# WSPRShield.net
KiCad netlist of a schematic drawn in Altium Designer
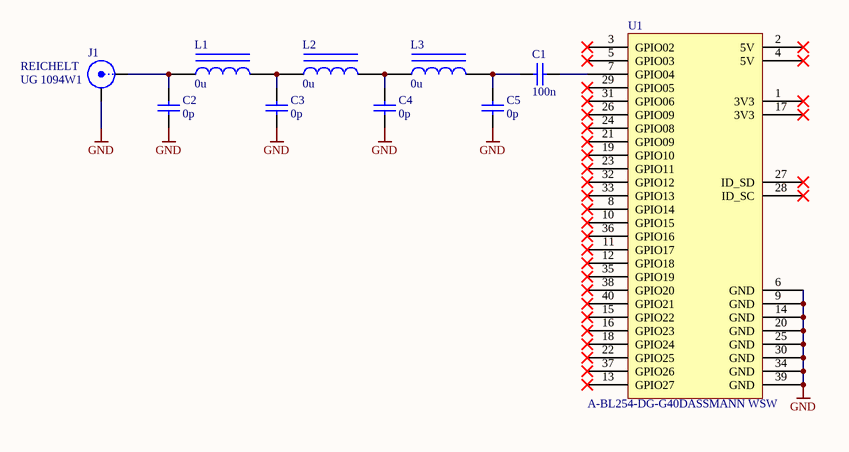
[diagram p0: WSPRShield.SchDoc]

(export (version "E")
  (design (tool "Eeschema 10.0.6"))
  (components
    (comp (ref "C1")
      (value "100n")
      (footprint "CER-CO-5MM")
      (fields
        (field (name "VOLTAGE") "100")
        (field (name "MANUFACTURER") "Miscellaneous")
        (field (name "Comment") "Capacitor")
      )
      (libsource (lib "ROLAND-LIB") (part "Capacitor"))
    )
    (comp (ref "C2")
      (value "0p")
      (footprint "CER-CO-5MM")
      (fields
        (field (name "VOLTAGE") "100")
        (field (name "MANUFACTURER") "Miscellaneous")
        (field (name "Comment") "Capacitor")
      )
      (libsource (lib "ROLAND-LIB") (part "Capacitor"))
    )
    (comp (ref "C3")
      (value "0p")
      (footprint "CER-CO-5MM")
      (fields
        (field (name "VOLTAGE") "100")
        (field (name "MANUFACTURER") "Miscellaneous")
        (field (name "Comment") "Capacitor")
      )
      (libsource (lib "ROLAND-LIB") (part "Capacitor"))
    )
    (comp (ref "C4")
      (value "0p")
      (footprint "CER-CO-5MM")
      (fields
        (field (name "VOLTAGE") "100")
        (field (name "MANUFACTURER") "Miscellaneous")
        (field (name "Comment") "Capacitor")
      )
      (libsource (lib "ROLAND-LIB") (part "Capacitor"))
    )
    (comp (ref "C5")
      (value "0p")
      (footprint "CER-CO-5MM")
      (fields
        (field (name "VOLTAGE") "100")
        (field (name "MANUFACTURER") "Miscellaneous")
        (field (name "Comment") "Capacitor")
      )
      (libsource (lib "ROLAND-LIB") (part "Capacitor"))
    )
    (comp (ref "J1")
      (value "COAX")
      (footprint "REICHELT_UG1094W1")
      (fields (field (name "MANUFACTURER") "REICHELT") (field (name "TYPE") "UG 1094W1"))
      (libsource (lib "ROLAND-LIB") (part "COAX"))
    )
    (comp (ref "L1")
      (value "0u")
      (footprint "T37-6")
      (fields (field (name "Comment") "Inductor (IronCore)"))
      (libsource (lib "ROLAND-LIB") (part "Inductor (IronCore)"))
    )
    (comp (ref "L2")
      (value "0u")
      (footprint "T37-6")
      (fields (field (name "Comment") "Inductor (IronCore)"))
      (libsource (lib "ROLAND-LIB") (part "Inductor (IronCore)"))
    )
    (comp (ref "L3")
      (value "0u")
      (footprint "T37-6")
      (fields (field (name "Comment") "Inductor (IronCore)"))
      (libsource (lib "ROLAND-LIB") (part "Inductor (IronCore)"))
    )
    (comp (ref "U1")
      (value "RaspberryPiB")
      (footprint "RASPI_BPHAT")
      (fields (field (name "TYPE") "A-BL254-DG-G40DASSMANN WSW") (field (name "MANUFACTURER") "ASSMANN"))
      (libsource (lib "ROLAND-LIB") (part "RaspberryPiB"))
    )
  )
  (nets
    (net (code "1") (name "GND") (class "Default")
      (node (ref "C2") (pin "1") (pinfunction "1_1") (pintype "passive"))
      (node (ref "C3") (pin "1") (pinfunction "1_1") (pintype "passive"))
      (node (ref "C4") (pin "1") (pinfunction "1_1") (pintype "passive"))
      (node (ref "C5") (pin "1") (pinfunction "1_1") (pintype "passive"))
      (node (ref "J1") (pin "2") (pinfunction "Y_2") (pintype "passive"))
      (node (ref "U1") (pin "14") (pinfunction "GND_14") (pintype "passive"))
      (node (ref "U1") (pin "20") (pinfunction "GND_20") (pintype "passive"))
      (node (ref "U1") (pin "25") (pinfunction "GND_25") (pintype "passive"))
      (node (ref "U1") (pin "30") (pinfunction "GND_30") (pintype "passive"))
      (node (ref "U1") (pin "34") (pinfunction "GND_34") (pintype "passive"))
      (node (ref "U1") (pin "39") (pinfunction "GND_39") (pintype "passive"))
      (node (ref "U1") (pin "6") (pinfunction "GND_6") (pintype "passive"))
      (node (ref "U1") (pin "9") (pinfunction "GND_9") (pintype "passive"))
    )
    (net (code "2") (name "Net-(C1-Pad2)") (class "Default")
      (node (ref "C1") (pin "2") (pinfunction "2_2") (pintype "passive"))
      (node (ref "C5") (pin "2") (pinfunction "2_2") (pintype "passive"))
      (node (ref "L3") (pin "2") (pinfunction "2_2") (pintype "passive"))
    )
    (net (code "3") (name "Net-(C3-Pad2)") (class "Default")
      (node (ref "C3") (pin "2") (pinfunction "2_2") (pintype "passive"))
      (node (ref "L1") (pin "2") (pinfunction "2_2") (pintype "passive"))
      (node (ref "L2") (pin "1") (pinfunction "1_1") (pintype "passive"))
    )
    (net (code "4") (name "Net-(C4-Pad2)") (class "Default")
      (node (ref "C4") (pin "2") (pinfunction "2_2") (pintype "passive"))
      (node (ref "L2") (pin "2") (pinfunction "2_2") (pintype "passive"))
      (node (ref "L3") (pin "1") (pinfunction "1_1") (pintype "passive"))
    )
    (net (code "5") (name "Net-(J1-X)") (class "Default")
      (node (ref "C2") (pin "2") (pinfunction "2_2") (pintype "passive"))
      (node (ref "J1") (pin "1") (pinfunction "X_1") (pintype "passive"))
      (node (ref "L1") (pin "1") (pinfunction "1_1") (pintype "passive"))
    )
    (net (code "6") (name "Net-(U1-GPIO04)") (class "Default")
      (node (ref "C1") (pin "1") (pinfunction "1_1") (pintype "passive"))
      (node (ref "U1") (pin "7") (pinfunction "GPIO04_7") (pintype "passive"))
    )
    (net (code "7") (name "unconnected-(U1-3V3-Pad1)") (class "Default")
      (node (ref "U1") (pin "1") (pinfunction "3V3_1") (pintype "passive+no_connect"))
    )
    (net (code "8") (name "unconnected-(U1-3V3-Pad17)") (class "Default")
      (node (ref "U1") (pin "17") (pinfunction "3V3_17") (pintype "passive+no_connect"))
    )
    (net (code "9") (name "unconnected-(U1-5V-Pad2)") (class "Default")
      (node (ref "U1") (pin "2") (pinfunction "5V_2") (pintype "passive+no_connect"))
    )
    (net (code "10") (name "unconnected-(U1-5V-Pad4)") (class "Default")
      (node (ref "U1") (pin "4") (pinfunction "5V_4") (pintype "passive+no_connect"))
    )
    (net (code "11") (name "unconnected-(U1-GPIO02-Pad3)") (class "Default")
      (node (ref "U1") (pin "3") (pinfunction "GPIO02_3") (pintype "passive+no_connect"))
    )
    (net (code "12") (name "unconnected-(U1-GPIO03-Pad5)") (class "Default")
      (node (ref "U1") (pin "5") (pinfunction "GPIO03_5") (pintype "passive+no_connect"))
    )
    (net (code "13") (name "unconnected-(U1-GPIO05-Pad29)") (class "Default")
      (node (ref "U1") (pin "29") (pinfunction "GPIO05_29") (pintype "passive+no_connect"))
    )
    (net (code "14") (name "unconnected-(U1-GPIO06-Pad31)") (class "Default")
      (node (ref "U1") (pin "31") (pinfunction "GPIO06_31") (pintype "passive+no_connect"))
    )
    (net (code "15") (name "unconnected-(U1-GPIO08-Pad24)") (class "Default")
      (node (ref "U1") (pin "24") (pinfunction "GPIO08_24") (pintype "passive+no_connect"))
    )
    (net (code "16") (name "unconnected-(U1-GPIO09-Pad21)") (class "Default")
      (node (ref "U1") (pin "21") (pinfunction "GPIO09_21") (pintype "passive+no_connect"))
    )
    (net (code "17") (name "unconnected-(U1-GPIO09-Pad26)") (class "Default")
      (node (ref "U1") (pin "26") (pinfunction "GPIO09_26") (pintype "passive+no_connect"))
    )
    (net (code "18") (name "unconnected-(U1-GPIO10-Pad19)") (class "Default")
      (node (ref "U1") (pin "19") (pinfunction "GPIO10_19") (pintype "passive+no_connect"))
    )
    (net (code "19") (name "unconnected-(U1-GPIO11-Pad23)") (class "Default")
      (node (ref "U1") (pin "23") (pinfunction "GPIO11_23") (pintype "passive+no_connect"))
    )
    (net (code "20") (name "unconnected-(U1-GPIO12-Pad32)") (class "Default")
      (node (ref "U1") (pin "32") (pinfunction "GPIO12_32") (pintype "passive+no_connect"))
    )
    (net (code "21") (name "unconnected-(U1-GPIO13-Pad33)") (class "Default")
      (node (ref "U1") (pin "33") (pinfunction "GPIO13_33") (pintype "passive+no_connect"))
    )
    (net (code "22") (name "unconnected-(U1-GPIO14-Pad8)") (class "Default")
      (node (ref "U1") (pin "8") (pinfunction "GPIO14_8") (pintype "passive+no_connect"))
    )
    (net (code "23") (name "unconnected-(U1-GPIO15-Pad10)") (class "Default")
      (node (ref "U1") (pin "10") (pinfunction "GPIO15_10") (pintype "passive+no_connect"))
    )
    (net (code "24") (name "unconnected-(U1-GPIO16-Pad36)") (class "Default")
      (node (ref "U1") (pin "36") (pinfunction "GPIO16_36") (pintype "passive+no_connect"))
    )
    (net (code "25") (name "unconnected-(U1-GPIO17-Pad11)") (class "Default")
      (node (ref "U1") (pin "11") (pinfunction "GPIO17_11") (pintype "passive+no_connect"))
    )
    (net (code "26") (name "unconnected-(U1-GPIO18-Pad12)") (class "Default")
      (node (ref "U1") (pin "12") (pinfunction "GPIO18_12") (pintype "passive+no_connect"))
    )
    (net (code "27") (name "unconnected-(U1-GPIO19-Pad35)") (class "Default")
      (node (ref "U1") (pin "35") (pinfunction "GPIO19_35") (pintype "passive+no_connect"))
    )
    (net (code "28") (name "unconnected-(U1-GPIO20-Pad38)") (class "Default")
      (node (ref "U1") (pin "38") (pinfunction "GPIO20_38") (pintype "passive+no_connect"))
    )
    (net (code "29") (name "unconnected-(U1-GPIO21-Pad40)") (class "Default")
      (node (ref "U1") (pin "40") (pinfunction "GPIO21_40") (pintype "passive+no_connect"))
    )
    (net (code "30") (name "unconnected-(U1-GPIO22-Pad15)") (class "Default")
      (node (ref "U1") (pin "15") (pinfunction "GPIO22_15") (pintype "passive+no_connect"))
    )
    (net (code "31") (name "unconnected-(U1-GPIO23-Pad16)") (class "Default")
      (node (ref "U1") (pin "16") (pinfunction "GPIO23_16") (pintype "passive+no_connect"))
    )
    (net (code "32") (name "unconnected-(U1-GPIO24-Pad18)") (class "Default")
      (node (ref "U1") (pin "18") (pinfunction "GPIO24_18") (pintype "passive+no_connect"))
    )
    (net (code "33") (name "unconnected-(U1-GPIO25-Pad22)") (class "Default")
      (node (ref "U1") (pin "22") (pinfunction "GPIO25_22") (pintype "passive+no_connect"))
    )
    (net (code "34") (name "unconnected-(U1-GPIO26-Pad37)") (class "Default")
      (node (ref "U1") (pin "37") (pinfunction "GPIO26_37") (pintype "passive+no_connect"))
    )
    (net (code "35") (name "unconnected-(U1-GPIO27-Pad13)") (class "Default")
      (node (ref "U1") (pin "13") (pinfunction "GPIO27_13") (pintype "passive+no_connect"))
    )
    (net (code "36") (name "unconnected-(U1-ID_SC-Pad28)") (class "Default")
      (node (ref "U1") (pin "28") (pinfunction "ID_SC_28") (pintype "passive+no_connect"))
    )
    (net (code "37") (name "unconnected-(U1-ID_SD-Pad27)") (class "Default")
      (node (ref "U1") (pin "27") (pinfunction "ID_SD_27") (pintype "passive+no_connect"))
    )
  )
)
